# schematic.net
KiCad netlist of a schematic drawn in Altium Designer
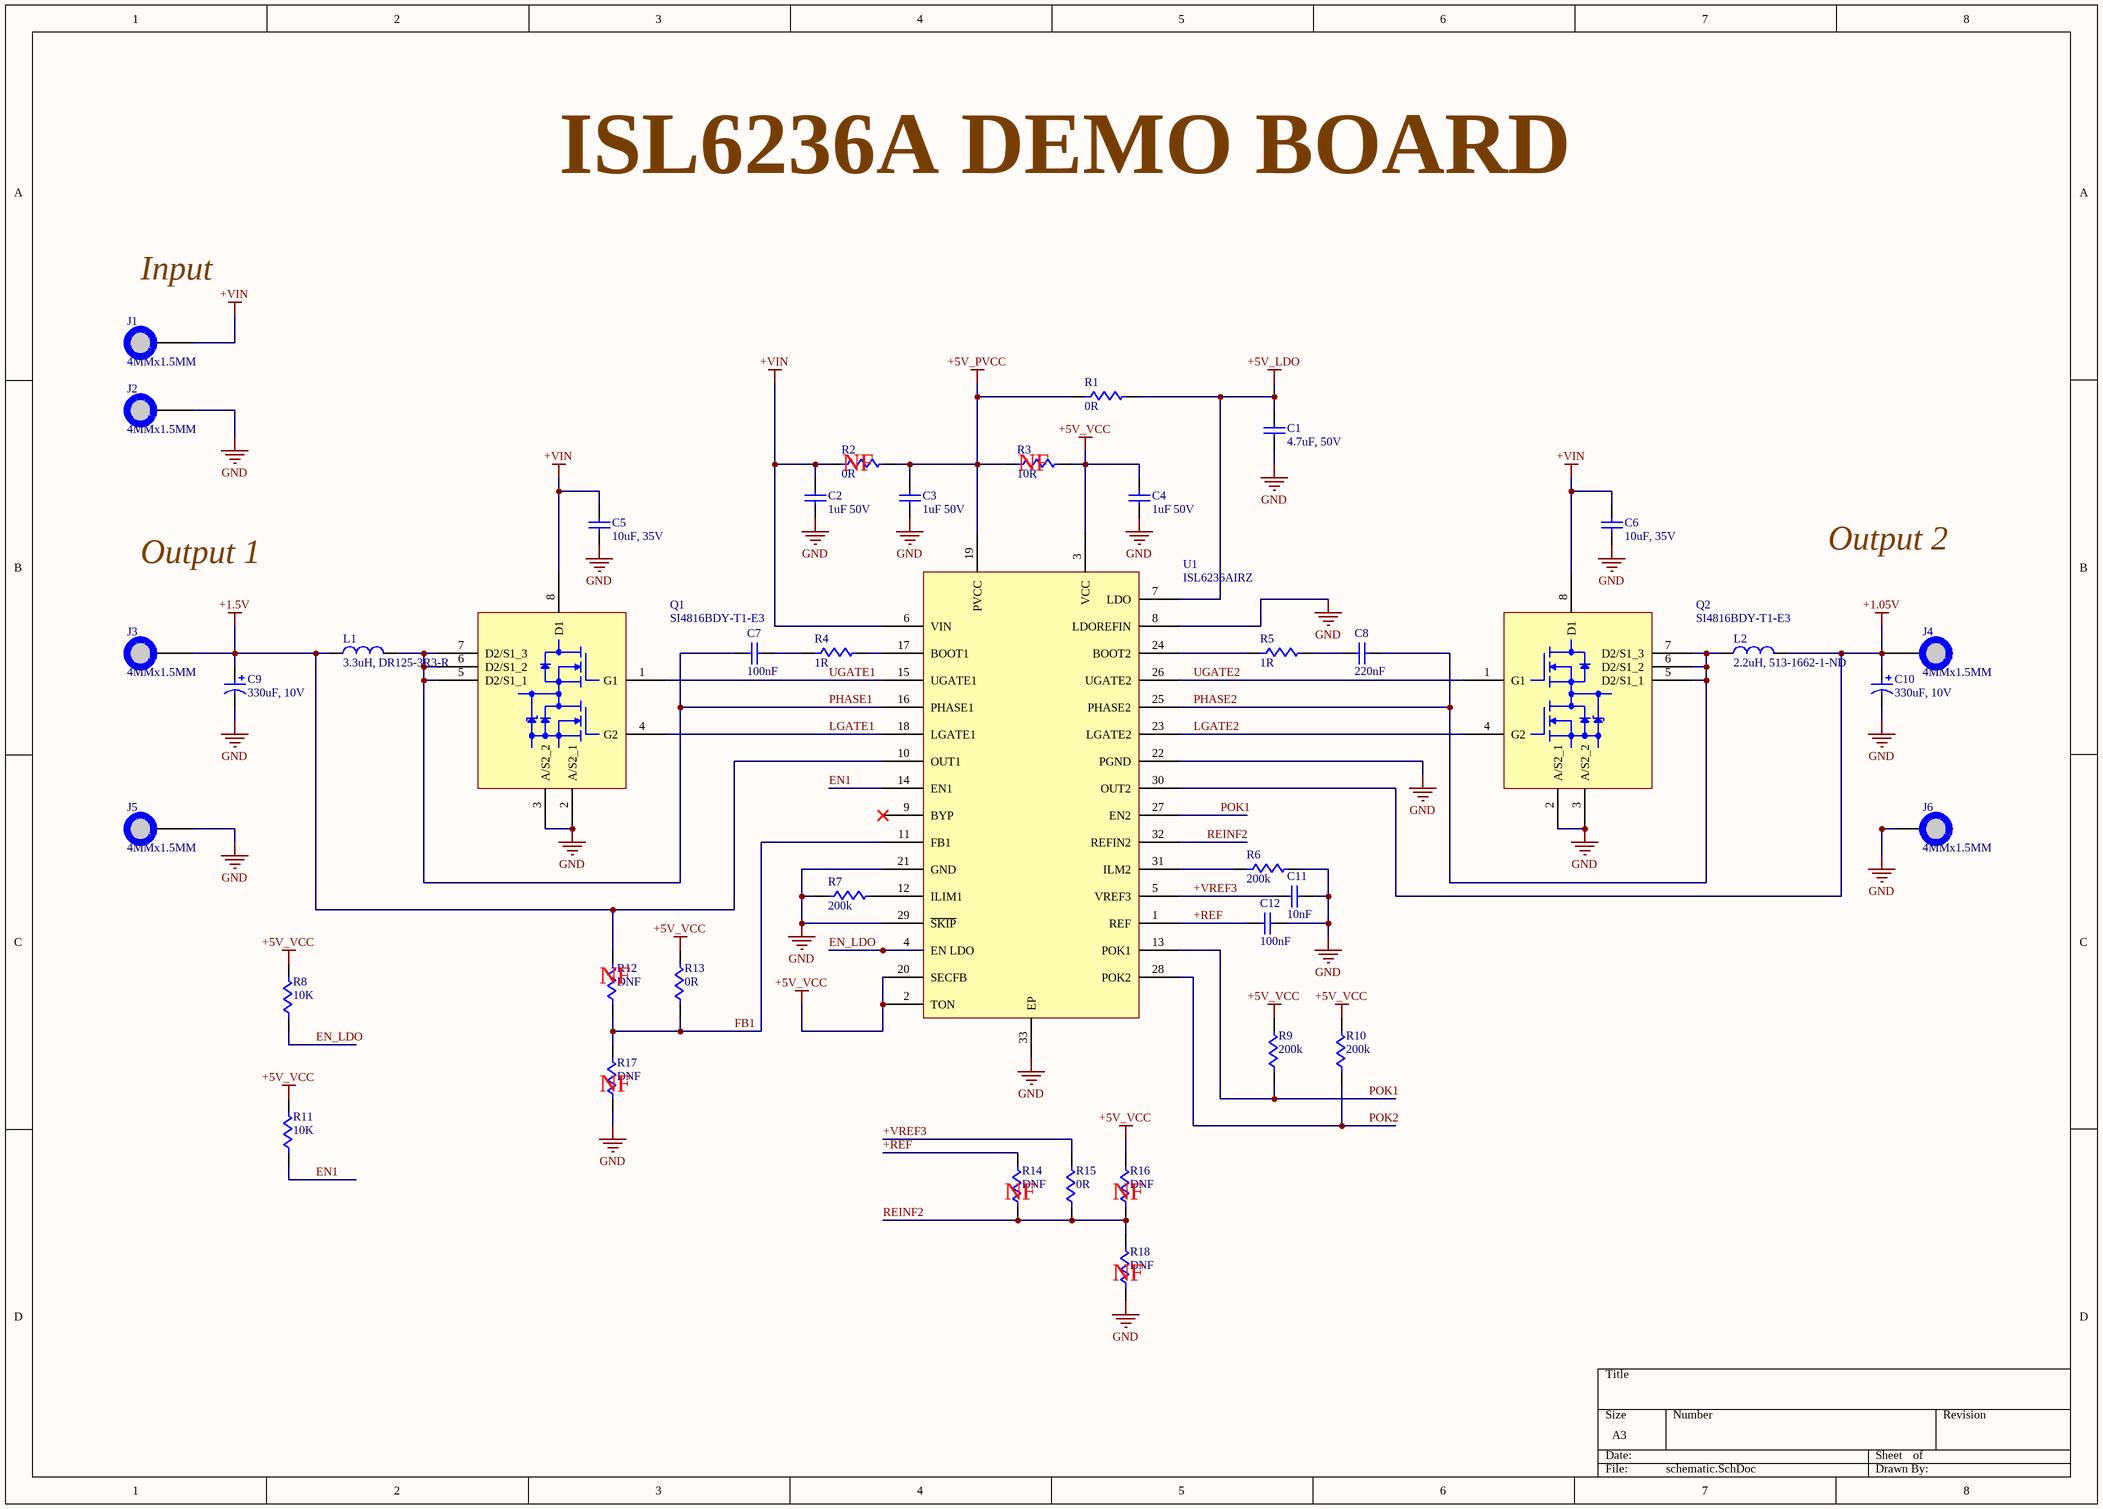
[diagram p0: schematic.SchDoc]

(export (version "E")
  (design (tool "Eeschema 10.0.6"))
  (components
    (comp (ref "C1")
      (value "4.7uF, 50V")
      (footprint "C1206")
      (description "C Series 1206 4.7 uF 50 V ±10 % Tolerance X5R SMT Multilayer Ceramic Capacitor")
      (fields
        (field (name "MANUFACTURER") "TDK")
        (field (name "MANUFACTURER PART NUMBER") "C3216X5R1H475K160AB")
      )
      (libsource (lib "default") (part "C3216X5R1H475K160AB"))
    )
    (comp (ref "C2")
      (value "1uF 50V")
      (footprint "C0805")
      (description "CAP CER 1UF 50V X7R 0805")
      (fields
        (field (name "MANUFACTURER") "KEMET")
        (field (name "MANUFACTURER PART NUMBER") "C0805C105K5RACTU")
      )
      (libsource (lib "default") (part "C0805C105K5RACTU"))
    )
    (comp (ref "C3")
      (value "1uF 50V")
      (footprint "C0805")
      (description "CAP CER 1UF 50V X7R 0805")
      (fields
        (field (name "MANUFACTURER") "KEMET")
        (field (name "MANUFACTURER PART NUMBER") "C0805C105K5RACTU")
      )
      (libsource (lib "default") (part "C0805C105K5RACTU"))
    )
    (comp (ref "C4")
      (value "1uF 50V")
      (footprint "C0805")
      (description "CAP CER 1UF 50V X7R 0805")
      (fields
        (field (name "MANUFACTURER") "KEMET")
        (field (name "MANUFACTURER PART NUMBER") "C0805C105K5RACTU")
      )
      (libsource (lib "default") (part "C0805C105K5RACTU"))
    )
    (comp (ref "C5")
      (value "10uF, 35V")
      (footprint "C1210")
      (fields
        (field (name "MANUFACTURER") "KEMET")
        (field (name "MANUFACTURER PART NUMBER") "C1210C106K6PACTU")
        (field (name "VOLTAGE") "35V")
      )
      (libsource (lib "default") (part "C1210C106K6PACTU"))
    )
    (comp (ref "C6")
      (value "10uF, 35V")
      (footprint "C1210")
      (fields
        (field (name "MANUFACTURER") "KEMET")
        (field (name "MANUFACTURER PART NUMBER") "C1210C106K6PACTU")
        (field (name "VOLTAGE") "35V")
      )
      (libsource (lib "default") (part "C1210C106K6PACTU"))
    )
    (comp (ref "C7")
      (value "100nF")
      (footprint "C0805")
      (description "Cap Ceramic 0.1uF 50V X7R 10% SMD 2.0 x 1.2 mm 125 C Paper T/R")
      (fields
        (field (name "MANUFACTURER") "KEMET")
        (field (name "MANUFACTURER PART NUMBER") "C0805C104K5RACTU")
      )
      (libsource (lib "default") (part "C0805C104K5RACTU"))
    )
    (comp (ref "C8")
      (value "220nF")
      (footprint "C0805")
      (description "CAP CER 0.22UF 50V X7R 0805")
      (fields
        (field (name "MANUFACTURER") "KEMET")
        (field (name "MANUFACTURER PART NUMBER") "C0805C224K5RACTU")
      )
      (libsource (lib "default") (part "C0805C224K5RACTU"))
    )
    (comp (ref "C9")
      (value "330uF, 10V")
      (footprint "7343-43")
      (description "Tantalum Capacitors - Polymer SMD 330uF 10volts 20%")
      (fields
        (field (name "MANUFACTURER") "KEMET")
        (field (name "MANUFACTURER PART NUMBER") "T530X337M010ATE004")
      )
      (libsource (lib "default") (part "T530X337M010ATE004"))
    )
    (comp (ref "C10")
      (value "330uF, 10V")
      (footprint "7343-43")
      (description "Tantalum Capacitors - Polymer SMD 330uF 10volts 20%")
      (fields
        (field (name "MANUFACTURER") "KEMET")
        (field (name "MANUFACTURER PART NUMBER") "T530X337M010ATE004")
      )
      (libsource (lib "default") (part "T530X337M010ATE004"))
    )
    (comp (ref "C11")
      (value "10nF")
      (footprint "C0805")
      (fields
        (field (name "MANUFACTURER") "KEMET")
        (field (name "MANUFACTURER PART NUMBER") "C0805F103K5RACTU")
        (field (name "TOLERANCE") "10%")
      )
      (libsource (lib "default") (part "C0805F103K5RACTU"))
    )
    (comp (ref "C12")
      (value "100nF")
      (footprint "C0805")
      (description "Cap Ceramic 0.1uF 50V X7R 10% SMD 2.0 x 1.2 mm 125 C Paper T/R")
      (fields
        (field (name "MANUFACTURER") "KEMET")
        (field (name "MANUFACTURER PART NUMBER") "C0805C104K5RACTU")
      )
      (libsource (lib "default") (part "C0805C104K5RACTU"))
    )
    (comp (ref "J1")
      (value "4MMx1.5MM")
      (footprint "PAD_WITH_HOLE_4mmx1.5mm")
      (description "Pad with a hole 4mm x 1.5mm")
      (libsource (lib "default") (part "PAD_WITH_HOLE_4mmx1.5mm"))
    )
    (comp (ref "J2")
      (value "4MMx1.5MM")
      (footprint "PAD_WITH_HOLE_4mmx1.5mm")
      (description "Pad with a hole 4mm x 1.5mm")
      (libsource (lib "default") (part "PAD_WITH_HOLE_4mmx1.5mm"))
    )
    (comp (ref "J3")
      (value "4MMx1.5MM")
      (footprint "PAD_WITH_HOLE_4mmx1.5mm")
      (description "Pad with a hole 4mm x 1.5mm")
      (libsource (lib "default") (part "PAD_WITH_HOLE_4mmx1.5mm"))
    )
    (comp (ref "J4")
      (value "4MMx1.5MM")
      (footprint "PAD_WITH_HOLE_4mmx1.5mm")
      (description "Pad with a hole 4mm x 1.5mm")
      (libsource (lib "default") (part "PAD_WITH_HOLE_4mmx1.5mm"))
    )
    (comp (ref "J5")
      (value "4MMx1.5MM")
      (footprint "PAD_WITH_HOLE_4mmx1.5mm")
      (description "Pad with a hole 4mm x 1.5mm")
      (libsource (lib "default") (part "PAD_WITH_HOLE_4mmx1.5mm"))
    )
    (comp (ref "J6")
      (value "4MMx1.5MM")
      (footprint "PAD_WITH_HOLE_4mmx1.5mm")
      (description "Pad with a hole 4mm x 1.5mm")
      (libsource (lib "default") (part "PAD_WITH_HOLE_4mmx1.5mm"))
    )
    (comp (ref "L1")
      (value "3.3uH, DR125-3R3-R")
      (footprint "DR125")
      (fields
        (field (name "MANUFACTURER") "Eaton Coiltronics")
        (field (name "MANUFACTURER PART NUMBER") "DR125-3R3-R")
        (field (name "TOLERANCE") "20%")
      )
      (libsource (lib "default") (part "DR125-3R3-R"))
    )
    (comp (ref "L2")
      (value "2.2uH, 513-1662-1-ND")
      (footprint "DR125")
      (description "FIXED IND 2.2UH 10.9A 4.5 MOHM")
      (fields
        (field (name "MANUFACTURER") "Eaton Cooper")
        (field (name "MANUFACTURER PART NUMBER") "DR125-2R2-R")
      )
      (libsource (lib "default") (part "DR125-2R2-R"))
    )
    (comp (ref "Q1")
      (value "SI4816BDY-T1-E3")
      (footprint "SO-8")
      (description "MOSFET 2N-CH 30V 5.8A 8-SOIC")
      (fields (field (name "MANUFACTURER") "Vishay Siliconix"))
      (libsource (lib "default") (part "SI4816BDY-T1-E3"))
    )
    (comp (ref "Q2")
      (value "SI4816BDY-T1-E3")
      (footprint "SO-8")
      (description "MOSFET 2N-CH 30V 5.8A 8-SOIC")
      (fields (field (name "MANUFACTURER") "Vishay Siliconix"))
      (libsource (lib "") (part "SI4816BDY-T1-E3_1"))
    )
    (comp (ref "R1")
      (value "0R")
      (footprint "R0805")
      (description "Thick Film Resistors - SMD 1/8W 0.0ohm 5%")
      (fields
        (field (name "MANUFACTURER") "Yageo")
        (field (name "MANUFACTURER PART NUMBER") "AC0805JR-070RL")
      )
      (libsource (lib "default") (part "AC0805JR-070RL"))
    )
    (comp (ref "R2")
      (value "0R")
      (footprint "R0805")
      (description "Thick Film Resistors - SMD 1/8W 0.0ohm 5%")
      (fields
        (field (name "MANUFACTURER") "Yageo")
        (field (name "MANUFACTURER PART NUMBER") "AC0805JR-070RL")
      )
      (libsource (lib "default") (part "AC0805JR-070RL"))
    )
    (comp (ref "R3")
      (value "10R")
      (footprint "R0805")
      (fields
        (field (name "MANUFACTURER") "Yageo")
        (field (name "MANUFACTURER PART NUMBER") "AC0805FR-0710RL")
        (field (name "TOLERANCE") "1%")
      )
      (libsource (lib "default") (part "AC0805FR-0710RL"))
    )
    (comp (ref "R4")
      (value "1R")
      (footprint "R0805")
      (description "RES SMD 1 OHM 1% 1/8W 0805")
      (fields
        (field (name "MANUFACTURER") "Yageo")
        (field (name "MANUFACTURER PART NUMBER") "AC0805FR-071RL")
      )
      (libsource (lib "default") (part "AC0805FR-071RL"))
    )
    (comp (ref "R5")
      (value "1R")
      (footprint "R0805")
      (description "RES SMD 1 OHM 1% 1/8W 0805")
      (fields
        (field (name "MANUFACTURER") "Yageo")
        (field (name "MANUFACTURER PART NUMBER") "AC0805FR-071RL")
      )
      (libsource (lib "default") (part "AC0805FR-071RL"))
    )
    (comp (ref "R6")
      (value "200k")
      (footprint "R0805")
      (description "Res Thick Film 0805 200K Ohm 1% 0.125W(1/8W) ±100ppm/C Epoxy Pad SMD Automotive T/R")
      (fields
        (field (name "MANUFACTURER") "Yageo")
        (field (name "MANUFACTURER PART NUMBER") "AC0805FR-07200KL")
      )
      (libsource (lib "default") (part "AC0805FR-07200KL"))
    )
    (comp (ref "R7")
      (value "200k")
      (footprint "R0805")
      (description "Res Thick Film 0805 200K Ohm 1% 0.125W(1/8W) ±100ppm/C Epoxy Pad SMD Automotive T/R")
      (fields
        (field (name "MANUFACTURER") "Yageo")
        (field (name "MANUFACTURER PART NUMBER") "AC0805FR-07200KL")
      )
      (libsource (lib "default") (part "AC0805FR-07200KL"))
    )
    (comp (ref "R8")
      (value "10K")
      (footprint "R0805")
      (description "RES SMD 10K OHM 1% 1/8W 0805")
      (fields
        (field (name "MANUFACTURER") "Yageo")
        (field (name "MANUFACTURER PART NUMBER") "AC0805FR-0710KL")
      )
      (libsource (lib "default") (part "AC0805FR-0710KL"))
    )
    (comp (ref "R9")
      (value "200k")
      (footprint "R0805")
      (description "Res Thick Film 0805 200K Ohm 1% 0.125W(1/8W) ±100ppm/C Epoxy Pad SMD Automotive T/R")
      (fields
        (field (name "MANUFACTURER") "Yageo")
        (field (name "MANUFACTURER PART NUMBER") "AC0805FR-07200KL")
      )
      (libsource (lib "default") (part "AC0805FR-07200KL"))
    )
    (comp (ref "R10")
      (value "200k")
      (footprint "R0805")
      (description "Res Thick Film 0805 200K Ohm 1% 0.125W(1/8W) ±100ppm/C Epoxy Pad SMD Automotive T/R")
      (fields
        (field (name "MANUFACTURER") "Yageo")
        (field (name "MANUFACTURER PART NUMBER") "AC0805FR-07200KL")
      )
      (libsource (lib "default") (part "AC0805FR-07200KL"))
    )
    (comp (ref "R11")
      (value "10K")
      (footprint "R0805")
      (description "RES SMD 10K OHM 1% 1/8W 0805")
      (fields
        (field (name "MANUFACTURER") "Yageo")
        (field (name "MANUFACTURER PART NUMBER") "AC0805FR-0710KL")
      )
      (libsource (lib "default") (part "AC0805FR-0710KL"))
    )
    (comp (ref "R12") (value "DNF") (footprint "R0805") (libsource (lib "default") (part "RES")))
    (comp (ref "R13")
      (value "0R")
      (footprint "R0805")
      (description "Thick Film Resistors - SMD 1/8W 0.0ohm 5%")
      (fields
        (field (name "MANUFACTURER") "Yageo")
        (field (name "MANUFACTURER PART NUMBER") "AC0805JR-070RL")
      )
      (libsource (lib "default") (part "AC0805JR-070RL"))
    )
    (comp (ref "R14") (value "DNF") (footprint "R0805") (libsource (lib "default") (part "RES")))
    (comp (ref "R15")
      (value "0R")
      (footprint "R0805")
      (description "Thick Film Resistors - SMD 1/8W 0.0ohm 5%")
      (fields
        (field (name "MANUFACTURER") "Yageo")
        (field (name "MANUFACTURER PART NUMBER") "AC0805JR-070RL")
      )
      (libsource (lib "default") (part "AC0805JR-070RL"))
    )
    (comp (ref "R16") (value "DNF") (footprint "R0805") (libsource (lib "default") (part "RES")))
    (comp (ref "R17") (value "DNF") (footprint "R0805") (libsource (lib "default") (part "RES")))
    (comp (ref "R18") (value "DNF") (footprint "R0805") (libsource (lib "default") (part "RES")))
    (comp (ref "U1")
      (value "ISL6236AIRZ")
      (footprint "L32.5x5B")
      (description "IC MAIN PWR CTRLR QUAD 32-QFN")
      (fields (field (name "MANUFACTURER") "Intersil"))
      (libsource (lib "default") (part "ISL6236AIRZ"))
    )
  )
  (nets
    (net (code "1") (name "+1.5V") (class "Default")
      (node (ref "C9") (pin "1") (pinfunction "1_1") (pintype "passive"))
      (node (ref "J3") (pin "1") (pinfunction "1_1") (pintype "passive"))
      (node (ref "L1") (pin "1") (pinfunction "1_1") (pintype "passive"))
      (node (ref "R12") (pin "2") (pinfunction "2_2") (pintype "passive"))
      (node (ref "U1") (pin "10") (pinfunction "OUT1_10") (pintype "passive"))
    )
    (net (code "2") (name "+1.05V") (class "Default")
      (node (ref "C10") (pin "1") (pinfunction "1_1") (pintype "passive"))
      (node (ref "J4") (pin "1") (pinfunction "1_1") (pintype "passive"))
      (node (ref "L2") (pin "2") (pinfunction "2_2") (pintype "passive"))
      (node (ref "U1") (pin "30") (pinfunction "OUT2_30") (pintype "passive"))
    )
    (net (code "3") (name "+5V_LDO") (class "Default")
      (node (ref "C1") (pin "2") (pinfunction "2_2") (pintype "passive"))
      (node (ref "R1") (pin "2") (pinfunction "2_2") (pintype "passive"))
      (node (ref "U1") (pin "7") (pinfunction "LDO_7") (pintype "passive"))
    )
    (net (code "4") (name "+5V_PVCC") (class "Default")
      (node (ref "C3") (pin "2") (pinfunction "2_2") (pintype "passive"))
      (node (ref "R1") (pin "1") (pinfunction "1_1") (pintype "passive"))
      (node (ref "R2") (pin "2") (pinfunction "2_2") (pintype "passive"))
      (node (ref "R3") (pin "1") (pinfunction "1_1") (pintype "passive"))
      (node (ref "U1") (pin "19") (pinfunction "PVCC_19") (pintype "passive"))
    )
    (net (code "5") (name "+5V_VCC") (class "Default")
      (node (ref "C4") (pin "2") (pinfunction "2_2") (pintype "passive"))
      (node (ref "R10") (pin "2") (pinfunction "2_2") (pintype "passive"))
      (node (ref "R11") (pin "2") (pinfunction "2_2") (pintype "passive"))
      (node (ref "R13") (pin "2") (pinfunction "2_2") (pintype "passive"))
      (node (ref "R16") (pin "2") (pinfunction "2_2") (pintype "passive"))
      (node (ref "R3") (pin "2") (pinfunction "2_2") (pintype "passive"))
      (node (ref "R8") (pin "2") (pinfunction "2_2") (pintype "passive"))
      (node (ref "R9") (pin "2") (pinfunction "2_2") (pintype "passive"))
      (node (ref "U1") (pin "2") (pinfunction "TON_2") (pintype "passive"))
      (node (ref "U1") (pin "20") (pinfunction "SECFB_20") (pintype "passive"))
      (node (ref "U1") (pin "3") (pinfunction "VCC_3") (pintype "passive"))
    )
    (net (code "6") (name "+VIN") (class "Default")
      (node (ref "C2") (pin "2") (pinfunction "2_2") (pintype "passive"))
      (node (ref "C5") (pin "2") (pinfunction "2_2") (pintype "passive"))
      (node (ref "C6") (pin "2") (pinfunction "2_2") (pintype "passive"))
      (node (ref "J1") (pin "1") (pinfunction "1_1") (pintype "passive"))
      (node (ref "Q1") (pin "8") (pinfunction "D1_8") (pintype "passive"))
      (node (ref "Q2") (pin "8") (pinfunction "D1_8") (pintype "passive"))
      (node (ref "R2") (pin "1") (pinfunction "1_1") (pintype "passive"))
      (node (ref "U1") (pin "6") (pinfunction "VIN_6") (pintype "passive"))
    )
    (net (code "7") (name "/+REF") (class "Default")
      (node (ref "C12") (pin "1") (pinfunction "1_1") (pintype "passive"))
      (node (ref "R14") (pin "2") (pinfunction "2_2") (pintype "passive"))
      (node (ref "U1") (pin "1") (pinfunction "REF_1") (pintype "passive"))
    )
    (net (code "8") (name "/+VREF3") (class "Default")
      (node (ref "C11") (pin "1") (pinfunction "1_1") (pintype "passive"))
      (node (ref "R15") (pin "2") (pinfunction "2_2") (pintype "passive"))
      (node (ref "U1") (pin "5") (pinfunction "VREF3_5") (pintype "passive"))
    )
    (net (code "9") (name "/EN1") (class "Default")
      (node (ref "R11") (pin "1") (pinfunction "1_1") (pintype "passive"))
      (node (ref "U1") (pin "14") (pinfunction "EN1_14") (pintype "passive"))
    )
    (net (code "10") (name "/EN_LDO") (class "Default")
      (node (ref "R8") (pin "1") (pinfunction "1_1") (pintype "passive"))
      (node (ref "U1") (pin "4") (pinfunction "EN_LDO_4") (pintype "passive"))
    )
    (net (code "11") (name "/FB1") (class "Default")
      (node (ref "R12") (pin "1") (pinfunction "1_1") (pintype "passive"))
      (node (ref "R13") (pin "1") (pinfunction "1_1") (pintype "passive"))
      (node (ref "R17") (pin "2") (pinfunction "2_2") (pintype "passive"))
      (node (ref "U1") (pin "11") (pinfunction "FB1_11") (pintype "passive"))
    )
    (net (code "12") (name "/LGATE1") (class "Default")
      (node (ref "Q1") (pin "4") (pinfunction "G2_4") (pintype "passive"))
      (node (ref "U1") (pin "18") (pinfunction "LGATE1_18") (pintype "passive"))
    )
    (net (code "13") (name "/LGATE2") (class "Default")
      (node (ref "Q2") (pin "4") (pinfunction "G2_4") (pintype "passive"))
      (node (ref "U1") (pin "23") (pinfunction "LGATE2_23") (pintype "passive"))
    )
    (net (code "14") (name "/PHASE1") (class "Default")
      (node (ref "C7") (pin "1") (pinfunction "1_1") (pintype "passive"))
      (node (ref "L1") (pin "2") (pinfunction "2_2") (pintype "passive"))
      (node (ref "Q1") (pin "5") (pinfunction "D2/S1_1_5") (pintype "passive"))
      (node (ref "Q1") (pin "6") (pinfunction "D2/S1_2_6") (pintype "passive"))
      (node (ref "Q1") (pin "7") (pinfunction "D2/S1_3_7") (pintype "passive"))
      (node (ref "U1") (pin "16") (pinfunction "PHASE1_16") (pintype "passive"))
    )
    (net (code "15") (name "/PHASE2") (class "Default")
      (node (ref "C8") (pin "2") (pinfunction "2_2") (pintype "passive"))
      (node (ref "L2") (pin "1") (pinfunction "1_1") (pintype "passive"))
      (node (ref "Q2") (pin "5") (pinfunction "D2/S1_1_5") (pintype "passive"))
      (node (ref "Q2") (pin "6") (pinfunction "D2/S1_2_6") (pintype "passive"))
      (node (ref "Q2") (pin "7") (pinfunction "D2/S1_3_7") (pintype "passive"))
      (node (ref "U1") (pin "25") (pinfunction "PHASE2_25") (pintype "passive"))
    )
    (net (code "16") (name "/POK1") (class "Default")
      (node (ref "R9") (pin "1") (pinfunction "1_1") (pintype "passive"))
      (node (ref "U1") (pin "13") (pinfunction "POK1_13") (pintype "passive"))
      (node (ref "U1") (pin "27") (pinfunction "EN2_27") (pintype "passive"))
    )
    (net (code "17") (name "/POK2") (class "Default")
      (node (ref "R10") (pin "1") (pinfunction "1_1") (pintype "passive"))
      (node (ref "U1") (pin "28") (pinfunction "POK2_28") (pintype "passive"))
    )
    (net (code "18") (name "/REINF2") (class "Default")
      (node (ref "R14") (pin "1") (pinfunction "1_1") (pintype "passive"))
      (node (ref "R15") (pin "1") (pinfunction "1_1") (pintype "passive"))
      (node (ref "R16") (pin "1") (pinfunction "1_1") (pintype "passive"))
      (node (ref "R18") (pin "2") (pinfunction "2_2") (pintype "passive"))
      (node (ref "U1") (pin "32") (pinfunction "REFIN2_32") (pintype "passive"))
    )
    (net (code "19") (name "/UGATE1") (class "Default")
      (node (ref "Q1") (pin "1") (pinfunction "G1_1") (pintype "passive"))
      (node (ref "U1") (pin "15") (pinfunction "UGATE1_15") (pintype "passive"))
    )
    (net (code "20") (name "/UGATE2") (class "Default")
      (node (ref "Q2") (pin "1") (pinfunction "G1_1") (pintype "passive"))
      (node (ref "U1") (pin "26") (pinfunction "UGATE2_26") (pintype "passive"))
    )
    (net (code "21") (name "GND") (class "Default")
      (node (ref "C1") (pin "1") (pinfunction "1_1") (pintype "passive"))
      (node (ref "C10") (pin "2") (pinfunction "2_2") (pintype "passive"))
      (node (ref "C11") (pin "2") (pinfunction "2_2") (pintype "passive"))
      (node (ref "C12") (pin "2") (pinfunction "2_2") (pintype "passive"))
      (node (ref "C2") (pin "1") (pinfunction "1_1") (pintype "passive"))
      (node (ref "C3") (pin "1") (pinfunction "1_1") (pintype "passive"))
      (node (ref "C4") (pin "1") (pinfunction "1_1") (pintype "passive"))
      (node (ref "C5") (pin "1") (pinfunction "1_1") (pintype "passive"))
      (node (ref "C6") (pin "1") (pinfunction "1_1") (pintype "passive"))
      (node (ref "C9") (pin "2") (pinfunction "2_2") (pintype "passive"))
      (node (ref "J2") (pin "1") (pinfunction "1_1") (pintype "passive"))
      (node (ref "J5") (pin "1") (pinfunction "1_1") (pintype "passive"))
      (node (ref "J6") (pin "1") (pinfunction "1_1") (pintype "passive"))
      (node (ref "Q1") (pin "2") (pinfunction "A/S2_1_2") (pintype "passive"))
      (node (ref "Q1") (pin "3") (pinfunction "A/S2_2_3") (pintype "passive"))
      (node (ref "Q2") (pin "2") (pinfunction "A/S2_1_2") (pintype "passive"))
      (node (ref "Q2") (pin "3") (pinfunction "A/S2_2_3") (pintype "passive"))
      (node (ref "R17") (pin "1") (pinfunction "1_1") (pintype "passive"))
      (node (ref "R18") (pin "1") (pinfunction "1_1") (pintype "passive"))
      (node (ref "R6") (pin "2") (pinfunction "2_2") (pintype "passive"))
      (node (ref "R7") (pin "1") (pinfunction "1_1") (pintype "passive"))
      (node (ref "U1") (pin "21") (pinfunction "GND_21") (pintype "passive"))
      (node (ref "U1") (pin "22") (pinfunction "PGND_22") (pintype "passive"))
      (node (ref "U1") (pin "29") (pinfunction "~{SKIP}_29") (pintype "passive"))
      (node (ref "U1") (pin "33") (pinfunction "EP_33") (pintype "passive"))
      (node (ref "U1") (pin "8") (pinfunction "LDOREFIN_8") (pintype "passive"))
    )
    (net (code "22") (name "Net-(C7-Pad2)") (class "Default")
      (node (ref "C7") (pin "2") (pinfunction "2_2") (pintype "passive"))
      (node (ref "R4") (pin "1") (pinfunction "1_1") (pintype "passive"))
    )
    (net (code "23") (name "Net-(C8-Pad1)") (class "Default")
      (node (ref "C8") (pin "1") (pinfunction "1_1") (pintype "passive"))
      (node (ref "R5") (pin "2") (pinfunction "2_2") (pintype "passive"))
    )
    (net (code "24") (name "Net-(U1-BOOT1)") (class "Default")
      (node (ref "R4") (pin "2") (pinfunction "2_2") (pintype "passive"))
      (node (ref "U1") (pin "17") (pinfunction "BOOT1_17") (pintype "passive"))
    )
    (net (code "25") (name "Net-(U1-BOOT2)") (class "Default")
      (node (ref "R5") (pin "1") (pinfunction "1_1") (pintype "passive"))
      (node (ref "U1") (pin "24") (pinfunction "BOOT2_24") (pintype "passive"))
    )
    (net (code "26") (name "Net-(U1-ILIM1)") (class "Default")
      (node (ref "R7") (pin "2") (pinfunction "2_2") (pintype "passive"))
      (node (ref "U1") (pin "12") (pinfunction "ILIM1_12") (pintype "passive"))
    )
    (net (code "27") (name "Net-(U1-ILM2)") (class "Default")
      (node (ref "R6") (pin "1") (pinfunction "1_1") (pintype "passive"))
      (node (ref "U1") (pin "31") (pinfunction "ILM2_31") (pintype "passive"))
    )
    (net (code "28") (name "unconnected-(U1-BYP-Pad9)") (class "Default")
      (node (ref "U1") (pin "9") (pinfunction "BYP_9") (pintype "passive+no_connect"))
    )
  )
)
